# CW308A_Generic_conns.net
KiCad netlist of a schematic drawn in Altium Designer
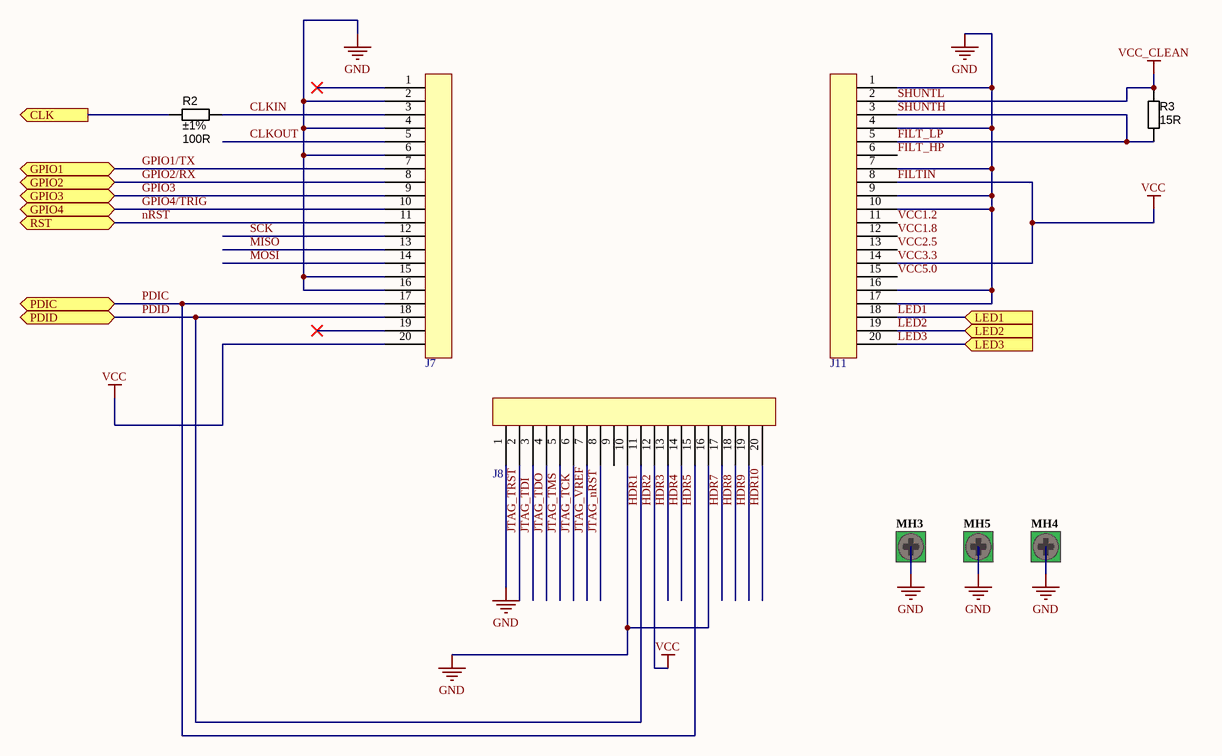
[diagram p0: CW308A_Generic_conns.SchDoc]

(export (version "E")
  (design (tool "Eeschema 10.0.6"))
  (components
    (comp (ref "J7")
      (value "20-Pin Header")
      (footprint "801-87-020-10-001101")
      (description "1x20 Header, Machined")
      (libsource (lib "") (part "801-87-020-10-001101_2"))
    )
    (comp (ref "J8")
      (value "20-Pin Header")
      (footprint "801-87-020-10-001101")
      (description "1x20 Header, Machined")
      (libsource (lib "NewAE_AltiumLib") (part "801-87-020-10-001101"))
    )
    (comp (ref "J11")
      (value "20-Pin Header")
      (footprint "801-87-020-10-001101")
      (description "1x20 Header, Machined")
      (libsource (lib "") (part "801-87-020-10-001101_1"))
    )
    (comp (ref "MH3")
      (value "Mounting-Hole-RND-Altium")
      (footprint "Mounting-Hole-RND-Altium")
      (description "Mounting Hole, Altium, 4.4mm pad, 3.4mm plated hole")
      (fields (field (name "PUBLISHER") "Altium"))
      (libsource (lib "Altium Content Vault") (part "CMP-0001-00029-1"))
    )
    (comp (ref "MH4")
      (value "Mounting-Hole-RND-Altium")
      (footprint "Mounting-Hole-RND-Altium")
      (description "Mounting Hole, Altium, 4.4mm pad, 3.4mm plated hole")
      (fields (field (name "PUBLISHER") "Altium"))
      (libsource (lib "Altium Content Vault") (part "CMP-0001-00029-1"))
    )
    (comp (ref "MH5")
      (value "Mounting-Hole-RND-Altium")
      (footprint "Mounting-Hole-RND-Altium")
      (description "Mounting Hole, Altium, 4.4mm pad, 3.4mm plated hole")
      (fields (field (name "PUBLISHER") "Altium"))
      (libsource (lib "Altium Content Vault") (part "CMP-0001-00029-1"))
    )
    (comp (ref "R2")
      (value "100R")
      (footprint "RESC1608X55N")
      (description "Resistor SMD chip 100 Ohm 0.1W 1% 0603")
      (fields (field (name "TOLERANCE") "±1%") (field (name "Comment") "Thick Film"))
      (libsource (lib "PBL - Resistors") (part "RES_100R_0603_1%"))
    )
    (comp (ref "R3")
      (value "15R")
      (footprint "RESC2012X70N")
      (description "Resistor SMD chip 15 Ohm 0.125W 5% 0805")
      (fields (field (name "TOLERANCE") "±5%") (field (name "Comment") "Thick Film"))
      (libsource (lib "PBL - Resistors") (part "RES_15R_0805_5%"))
    )
  )
  (nets
    (net (code "1") (name "/CLK") (class "Default")
      (node (ref "R2") (pin "1") (pinfunction "1_1") (pintype "passive"))
    )
    (net (code "2") (name "/CLKIN") (class "Default")
      (node (ref "J7") (pin "3") (pintype "passive"))
      (node (ref "R2") (pin "2") (pinfunction "2_2") (pintype "passive"))
    )
    (net (code "3") (name "/CLKOUT") (class "Default") (node (ref "J7") (pin "5") (pintype "passive")))
    (net (code "4") (name "/FILT_HP") (class "Default") (node (ref "J11") (pin "6") (pintype "passive")))
    (net (code "5") (name "/FILT_LP") (class "Default")
      (node (ref "J11") (pin "3") (pintype "passive"))
      (node (ref "J11") (pin "5") (pintype "passive"))
      (node (ref "R3") (pin "2") (pinfunction "2_2") (pintype "passive"))
    )
    (net (code "6") (name "/GPIO1{slash}TX") (class "Default")
      (node (ref "J7") (pin "7") (pintype "passive"))
    )
    (net (code "7") (name "/GPIO2{slash}RX") (class "Default")
      (node (ref "J7") (pin "8") (pintype "passive"))
    )
    (net (code "8") (name "/GPIO3") (class "Default") (node (ref "J7") (pin "9") (pintype "passive")))
    (net (code "9") (name "/GPIO4{slash}TRIG") (class "Default")
      (node (ref "J7") (pin "10") (pintype "passive"))
    )
    (net (code "10") (name "/HDR1") (class "Default")
      (node (ref "J7") (pin "18") (pintype "passive"))
      (node (ref "J8") (pin "11") (pintype "passive"))
    )
    (net (code "11") (name "/HDR3") (class "Default") (node (ref "J8") (pin "13") (pintype "passive")))
    (net (code "12") (name "/HDR4") (class "Default") (node (ref "J8") (pin "14") (pintype "passive")))
    (net (code "13") (name "/HDR5") (class "Default")
      (node (ref "J7") (pin "17") (pintype "passive"))
      (node (ref "J8") (pin "15") (pintype "passive"))
    )
    (net (code "14") (name "/HDR7") (class "Default") (node (ref "J8") (pin "17") (pintype "passive")))
    (net (code "15") (name "/HDR8") (class "Default") (node (ref "J8") (pin "18") (pintype "passive")))
    (net (code "16") (name "/HDR9") (class "Default") (node (ref "J8") (pin "19") (pintype "passive")))
    (net (code "17") (name "/HDR10") (class "Default") (node (ref "J8") (pin "20") (pintype "passive")))
    (net (code "18") (name "/JTAG_TCK") (class "Default") (node (ref "J8") (pin "6") (pintype "passive")))
    (net (code "19") (name "/JTAG_TDI") (class "Default") (node (ref "J8") (pin "3") (pintype "passive")))
    (net (code "20") (name "/JTAG_TDO") (class "Default") (node (ref "J8") (pin "4") (pintype "passive")))
    (net (code "21") (name "/JTAG_TMS") (class "Default") (node (ref "J8") (pin "5") (pintype "passive")))
    (net (code "22") (name "/JTAG_TRST") (class "Default") (node (ref "J8") (pin "2") (pintype "passive")))
    (net (code "23") (name "/JTAG_VREF") (class "Default") (node (ref "J8") (pin "7") (pintype "passive")))
    (net (code "24") (name "/JTAG_nRST") (class "Default") (node (ref "J8") (pin "8") (pintype "passive")))
    (net (code "25") (name "/LED1") (class "Default") (node (ref "J11") (pin "18") (pintype "passive")))
    (net (code "26") (name "/LED2") (class "Default") (node (ref "J11") (pin "19") (pintype "passive")))
    (net (code "27") (name "/LED3") (class "Default") (node (ref "J11") (pin "20") (pintype "passive")))
    (net (code "28") (name "/MISO") (class "Default") (node (ref "J7") (pin "13") (pintype "passive")))
    (net (code "29") (name "/MOSI") (class "Default") (node (ref "J7") (pin "14") (pintype "passive")))
    (net (code "30") (name "/SCK") (class "Default") (node (ref "J7") (pin "12") (pintype "passive")))
    (net (code "31") (name "/VCC1.2") (class "Default") (node (ref "J11") (pin "11") (pintype "passive")))
    (net (code "32") (name "/VCC1.8") (class "Default") (node (ref "J11") (pin "12") (pintype "passive")))
    (net (code "33") (name "/VCC2.5") (class "Default") (node (ref "J11") (pin "13") (pintype "passive")))
    (net (code "34") (name "/VCC5.0") (class "Default") (node (ref "J11") (pin "15") (pintype "passive")))
    (net (code "35") (name "/nRST") (class "Default") (node (ref "J7") (pin "11") (pintype "passive")))
    (net (code "36") (name "GND") (class "Default")
      (node (ref "J11") (pin "1") (pintype "passive"))
      (node (ref "J11") (pin "10") (pintype "passive"))
      (node (ref "J11") (pin "16") (pintype "passive"))
      (node (ref "J11") (pin "17") (pintype "passive"))
      (node (ref "J11") (pin "4") (pintype "passive"))
      (node (ref "J11") (pin "7") (pintype "passive"))
      (node (ref "J11") (pin "9") (pintype "passive"))
      (node (ref "J7") (pin "15") (pintype "passive"))
      (node (ref "J7") (pin "16") (pintype "passive"))
      (node (ref "J7") (pin "2") (pintype "passive"))
      (node (ref "J7") (pin "4") (pintype "passive"))
      (node (ref "J7") (pin "6") (pintype "passive"))
      (node (ref "J8") (pin "1") (pintype "passive"))
      (node (ref "J8") (pin "10") (pintype "passive"))
      (node (ref "J8") (pin "16") (pintype "passive"))
      (node (ref "MH3") (pin "1") (pinfunction "1_1") (pintype "passive"))
      (node (ref "MH4") (pin "1") (pinfunction "1_1") (pintype "passive"))
      (node (ref "MH5") (pin "1") (pinfunction "1_1") (pintype "passive"))
    )
    (net (code "37") (name "VCC") (class "Default")
      (node (ref "J11") (pin "14") (pintype "passive"))
      (node (ref "J11") (pin "8") (pintype "passive"))
      (node (ref "J7") (pin "20") (pintype "passive"))
      (node (ref "J8") (pin "12") (pintype "passive"))
    )
    (net (code "38") (name "VCC_CLEAN") (class "Default")
      (node (ref "J11") (pin "2") (pintype "passive"))
      (node (ref "R3") (pin "1") (pinfunction "1_1") (pintype "passive"))
    )
    (net (code "39") (name "unconnected-(J7-Pad1)") (class "Default")
      (node (ref "J7") (pin "1") (pintype "passive+no_connect"))
    )
    (net (code "40") (name "unconnected-(J7-Pad19)") (class "Default")
      (node (ref "J7") (pin "19") (pintype "passive+no_connect"))
    )
    (net (code "41") (name "unconnected-(J8-Pad9)") (class "Default")
      (node (ref "J8") (pin "9") (pintype "passive"))
    )
  )
)
